# DfPlayer_board.net
KiCad netlist of a schematic drawn in Altium Designer
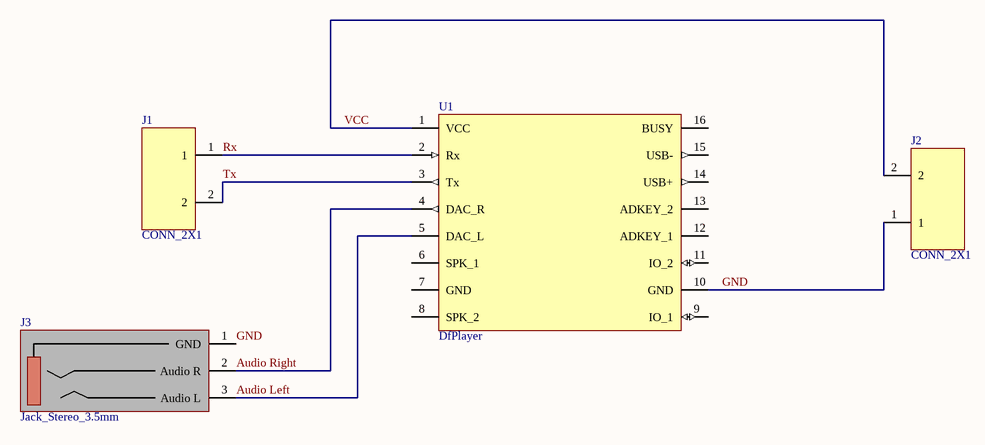
[diagram p0: DfPlayer_board.SchDoc]

(export (version "E")
  (design (tool "Eeschema 10.0.6"))
  (components
    (comp (ref "J1")
      (value "CONN_2X1")
      (description "Connector 2 vias 1 Row")
      (libsource (lib "") (part "CONN_2X1_1"))
    )
    (comp (ref "J2")
      (value "CONN_2X1")
      (description "Connector 2 vias 1 Row")
      (libsource (lib "DfPlayer_board") (part "CONN_2X1"))
    )
    (comp (ref "J3")
      (value "Jack_Stereo_3.5mm")
      (description "Conector Jack stereo 3.5mm sin microfono")
      (libsource (lib "DfPlayer_board") (part "Jack_Stereo_3.5mm"))
    )
    (comp (ref "U1")
      (value "DfPlayer")
      (description "Header for DfPlayer mini MP3 2x8 pins")
      (libsource (lib "DfPlayer_board") (part "DfPlayer"))
    )
  )
  (nets
    (net (code "1") (name "/Audio Left") (class "Default")
      (node (ref "J3") (pin "3") (pinfunction "Audio_L_3") (pintype "passive"))
      (node (ref "U1") (pin "5") (pinfunction "DAC_L_5") (pintype "passive"))
    )
    (net (code "2") (name "/Audio Right") (class "Default")
      (node (ref "J3") (pin "2") (pinfunction "Audio_R_2") (pintype "passive"))
      (node (ref "U1") (pin "4") (pinfunction "DAC_R_4") (pintype "output"))
    )
    (net (code "3") (name "/GND") (class "Default")
      (node (ref "J2") (pin "1") (pinfunction "1_1") (pintype "passive"))
      (node (ref "J3") (pin "1") (pinfunction "GND_1") (pintype "power_in"))
      (node (ref "U1") (pin "10") (pinfunction "GND_10") (pintype "power_in"))
    )
    (net (code "4") (name "/Rx") (class "Default")
      (node (ref "J1") (pin "1") (pinfunction "1_1") (pintype "passive"))
      (node (ref "U1") (pin "2") (pinfunction "Rx_2") (pintype "input"))
    )
    (net (code "5") (name "/Tx") (class "Default")
      (node (ref "J1") (pin "2") (pinfunction "2_2") (pintype "passive"))
      (node (ref "U1") (pin "3") (pinfunction "Tx_3") (pintype "output"))
    )
    (net (code "6") (name "/VCC") (class "Default")
      (node (ref "J2") (pin "2") (pinfunction "2_2") (pintype "passive"))
      (node (ref "U1") (pin "1") (pinfunction "VCC_1") (pintype "passive"))
    )
    (net (code "7") (name "unconnected-(U1-ADKEY_1-Pad12)") (class "Default")
      (node (ref "U1") (pin "12") (pinfunction "ADKEY_1_12") (pintype "passive"))
    )
    (net (code "8") (name "unconnected-(U1-ADKEY_2-Pad13)") (class "Default")
      (node (ref "U1") (pin "13") (pinfunction "ADKEY_2_13") (pintype "passive"))
    )
    (net (code "9") (name "unconnected-(U1-BUSY-Pad16)") (class "Default")
      (node (ref "U1") (pin "16") (pinfunction "BUSY_16") (pintype "passive"))
    )
    (net (code "10") (name "unconnected-(U1-GND-Pad7)") (class "Default")
      (node (ref "U1") (pin "7") (pinfunction "GND_7") (pintype "power_in"))
    )
    (net (code "11") (name "unconnected-(U1-IO_1-Pad9)") (class "Default")
      (node (ref "U1") (pin "9") (pinfunction "IO_1_9") (pintype "bidirectional"))
    )
    (net (code "12") (name "unconnected-(U1-IO_2-Pad11)") (class "Default")
      (node (ref "U1") (pin "11") (pinfunction "IO_2_11") (pintype "bidirectional"))
    )
    (net (code "13") (name "unconnected-(U1-SPK_1-Pad6)") (class "Default")
      (node (ref "U1") (pin "6") (pinfunction "SPK_1_6") (pintype "passive"))
    )
    (net (code "14") (name "unconnected-(U1-SPK_2-Pad8)") (class "Default")
      (node (ref "U1") (pin "8") (pinfunction "SPK_2_8") (pintype "passive"))
    )
    (net (code "15") (name "unconnected-(U1-USB+-Pad14)") (class "Default")
      (node (ref "U1") (pin "14") (pinfunction "USB+_14") (pintype "output"))
    )
    (net (code "16") (name "unconnected-(U1-USB--Pad15)") (class "Default")
      (node (ref "U1") (pin "15") (pinfunction "USB-_15") (pintype "output"))
    )
  )
)
